# STM32F030.net
KiCad netlist of a schematic drawn in EAGLE
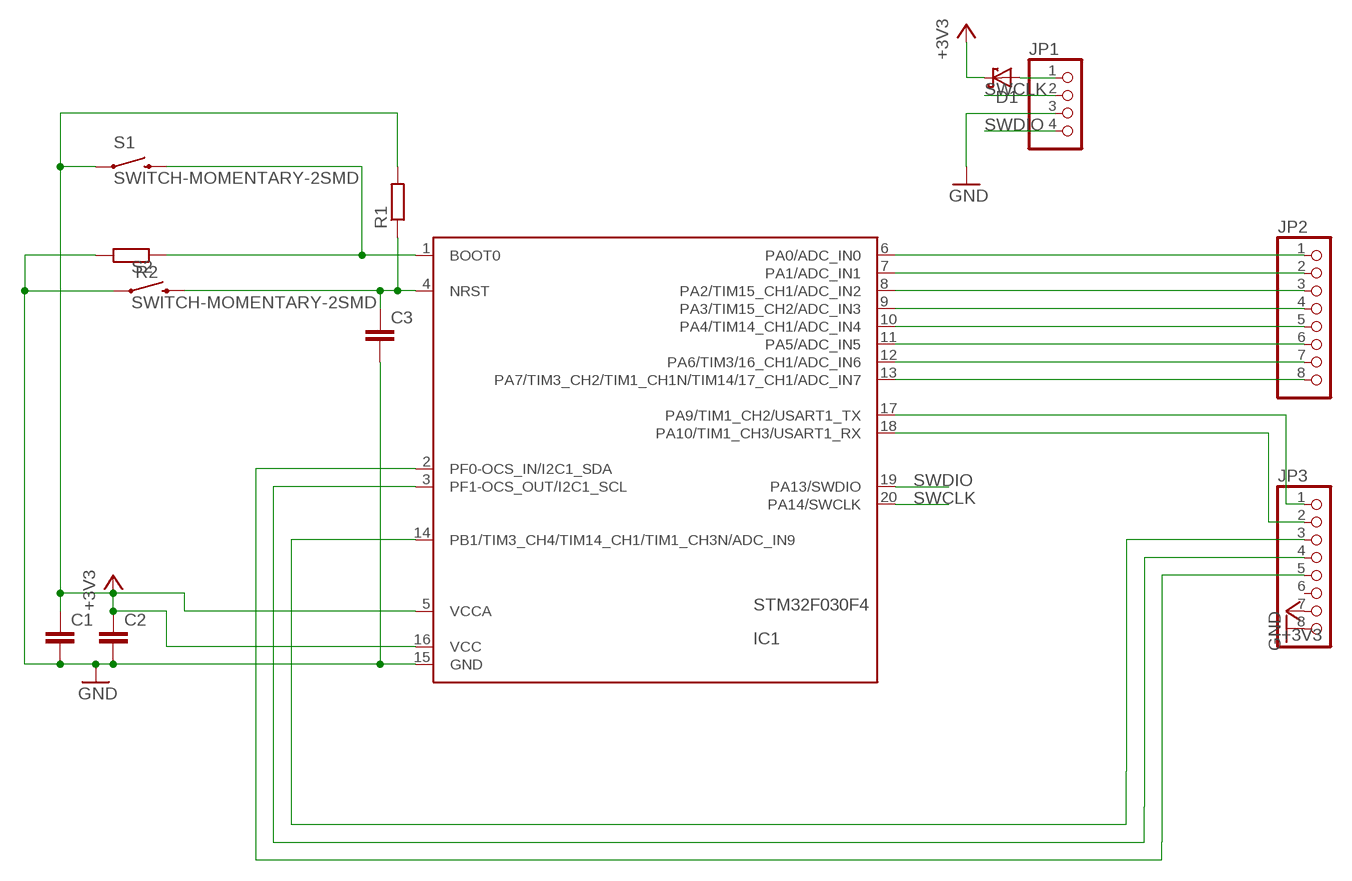
[diagram p0: schematic, sheet 1]

(export (version "E")
  (design (tool "Eeschema 10.0.6"))
  (components
    (comp (ref "C1")
      (value "CAP_0805")
      (footprint "eagle-import:C0805")
      (libsource (lib "eagle-import") (part "CAP_0805"))
    )
    (comp (ref "C2")
      (value "CAP_0805")
      (footprint "eagle-import:C0805")
      (libsource (lib "eagle-import") (part "CAP_0805"))
    )
    (comp (ref "C3")
      (value "CAP_0805")
      (footprint "eagle-import:C0805")
      (libsource (lib "eagle-import") (part "CAP_0805"))
    )
    (comp (ref "D1")
      (value "DIODE-SH_SOD523")
      (footprint "eagle-import:SOD523")
      (libsource (lib "eagle-import") (part "DIODE-SH_SOD523"))
    )
    (comp (ref "IC1")
      (value "STM32F030F4")
      (footprint "eagle-import:TSSOP20")
      (libsource (lib "eagle-import") (part "STM32F030F4"))
    )
    (comp (ref "JP1")
      (value "PINHD-1X4")
      (footprint "eagle-import:1X04")
      (libsource (lib "eagle-import") (part "PINHD-1X4"))
    )
    (comp (ref "JP2")
      (value "PINHD-1X8")
      (footprint "eagle-import:1X08")
      (libsource (lib "eagle-import") (part "PINHD-1X8"))
    )
    (comp (ref "JP3")
      (value "PINHD-1X8")
      (footprint "eagle-import:1X08")
      (libsource (lib "eagle-import") (part "PINHD-1X8"))
    )
    (comp (ref "R1")
      (value "R_0805")
      (footprint "eagle-import:R0805")
      (libsource (lib "eagle-import") (part "R_0805"))
    )
    (comp (ref "R2")
      (value "R_0805")
      (footprint "eagle-import:R0805")
      (libsource (lib "eagle-import") (part "R_0805"))
    )
    (comp (ref "S1")
      (value "SWITCH-MOMENTARY-2SMD")
      (footprint "eagle-import:TACTILE-SWITCH-SMD")
      (libsource (lib "eagle-import") (part "SWITCH-MOMENTARY-2SMD"))
    )
    (comp (ref "S2")
      (value "SWITCH-MOMENTARY-2SMD")
      (footprint "eagle-import:TACTILE-SWITCH-SMD")
      (libsource (lib "eagle-import") (part "SWITCH-MOMENTARY-2SMD"))
    )
  )
  (nets
    (net (code "1") (name "+3V3") (class "Default")
      (node (ref "C1") (pin "1") (pinfunction "1_1") (pintype "passive"))
      (node (ref "C2") (pin "1") (pinfunction "1_1") (pintype "passive"))
      (node (ref "D1") (pin "C") (pinfunction "C_C") (pintype "passive"))
      (node (ref "IC1") (pin "16") (pinfunction "VCC_16") (pintype "power_in"))
      (node (ref "IC1") (pin "5") (pinfunction "VCCA_5") (pintype "power_in"))
      (node (ref "JP3") (pin "7") (pinfunction "7_7") (pintype "passive"))
      (node (ref "R1") (pin "2") (pinfunction "2_2") (pintype "passive"))
      (node (ref "S1") (pin "1") (pinfunction "1_1") (pintype "passive"))
    )
    (net (code "2") (name "/SWCLK") (class "Default")
      (node (ref "IC1") (pin "20") (pinfunction "PA14/SWCLK_20") (pintype "bidirectional"))
      (node (ref "JP1") (pin "2") (pinfunction "2_2") (pintype "passive"))
    )
    (net (code "3") (name "/SWDIO") (class "Default")
      (node (ref "IC1") (pin "19") (pinfunction "PA13/SWDIO_19") (pintype "bidirectional"))
      (node (ref "JP1") (pin "4") (pinfunction "4_4") (pintype "passive"))
    )
    (net (code "4") (name "GND") (class "Default")
      (node (ref "C1") (pin "2") (pinfunction "2_2") (pintype "passive"))
      (node (ref "C2") (pin "2") (pinfunction "2_2") (pintype "passive"))
      (node (ref "C3") (pin "2") (pinfunction "2_2") (pintype "passive"))
      (node (ref "IC1") (pin "15") (pinfunction "GND_15") (pintype "power_in"))
      (node (ref "JP1") (pin "3") (pinfunction "3_3") (pintype "passive"))
      (node (ref "JP3") (pin "8") (pinfunction "8_8") (pintype "passive"))
      (node (ref "R2") (pin "2") (pinfunction "2_2") (pintype "passive"))
      (node (ref "S2") (pin "1") (pinfunction "1_1") (pintype "passive"))
    )
    (net (code "5") (name "Net-(D1-PadA)") (class "Default")
      (node (ref "D1") (pin "A") (pinfunction "A_A") (pintype "passive"))
      (node (ref "JP1") (pin "1") (pinfunction "1_1") (pintype "passive"))
    )
    (net (code "6") (name "Net-(IC1-BOOT0)") (class "Default")
      (node (ref "IC1") (pin "1") (pinfunction "BOOT0_1") (pintype "bidirectional"))
      (node (ref "R2") (pin "1") (pinfunction "1_1") (pintype "passive"))
      (node (ref "S1") (pin "3") (pinfunction "2_3") (pintype "passive"))
    )
    (net (code "7") (name "Net-(IC1-NRST)") (class "Default")
      (node (ref "C3") (pin "1") (pinfunction "1_1") (pintype "passive"))
      (node (ref "IC1") (pin "4") (pinfunction "NRST_4") (pintype "bidirectional"))
      (node (ref "R1") (pin "1") (pinfunction "1_1") (pintype "passive"))
      (node (ref "S2") (pin "3") (pinfunction "2_3") (pintype "passive"))
    )
    (net (code "8") (name "Net-(IC1-PA0{slash}ADC_IN0)") (class "Default")
      (node (ref "IC1") (pin "6") (pinfunction "PA0/ADC_IN0_6") (pintype "bidirectional"))
      (node (ref "JP2") (pin "1") (pinfunction "1_1") (pintype "passive"))
    )
    (net (code "9") (name "Net-(IC1-PA1{slash}ADC_IN1)") (class "Default")
      (node (ref "IC1") (pin "7") (pinfunction "PA1/ADC_IN1_7") (pintype "bidirectional"))
      (node (ref "JP2") (pin "2") (pinfunction "2_2") (pintype "passive"))
    )
    (net (code "10") (name "Net-(IC1-PA2{slash}TIM15_CH1{slash}ADC_IN2)") (class "Default")
      (node (ref "IC1") (pin "8") (pinfunction "PA2/TIM15_CH1/ADC_IN2_8") (pintype "bidirectional"))
      (node (ref "JP2") (pin "3") (pinfunction "3_3") (pintype "passive"))
    )
    (net (code "11") (name "Net-(IC1-PA3{slash}TIM15_CH2{slash}ADC_IN3)") (class "Default")
      (node (ref "IC1") (pin "9") (pinfunction "PA3/TIM15_CH2/ADC_IN3_9") (pintype "bidirectional"))
      (node (ref "JP2") (pin "4") (pinfunction "4_4") (pintype "passive"))
    )
    (net (code "12") (name "Net-(IC1-PA4{slash}TIM14_CH1{slash}ADC_IN4)") (class "Default")
      (node (ref "IC1") (pin "10") (pinfunction "PA4/TIM14_CH1/ADC_IN4_10") (pintype "bidirectional"))
      (node (ref "JP2") (pin "5") (pinfunction "5_5") (pintype "passive"))
    )
    (net (code "13") (name "Net-(IC1-PA5{slash}ADC_IN5)") (class "Default")
      (node (ref "IC1") (pin "11") (pinfunction "PA5/ADC_IN5_11") (pintype "bidirectional"))
      (node (ref "JP2") (pin "6") (pinfunction "6_6") (pintype "passive"))
    )
    (net (code "14") (name "Net-(IC1-PA6{slash}TIM3{slash}16_CH1{slash}ADC_IN6)") (class "Default")
      (node (ref "IC1") (pin "12") (pinfunction "PA6/TIM3/16_CH1/ADC_IN6_12") (pintype "bidirectional"))
      (node (ref "JP2") (pin "7") (pinfunction "7_7") (pintype "passive"))
    )
    (net (code "15") (name "Net-(IC1-PA7{slash}TIM3_CH2{slash}TIM1_CH1N{slash}TIM14{slash}17_CH1{slash}ADC_IN7)") (class "Default")
      (node (ref "IC1") (pin "13") (pinfunction "PA7/TIM3_CH2/TIM1_CH1N/TIM14/17_CH1/ADC_IN7_13") (pintype "bidirectional"))
      (node (ref "JP2") (pin "8") (pinfunction "8_8") (pintype "passive"))
    )
    (net (code "16") (name "Net-(IC1-PA9{slash}TIM1_CH2{slash}USART1_TX)") (class "Default")
      (node (ref "IC1") (pin "17") (pinfunction "PA9/TIM1_CH2/USART1_TX_17") (pintype "bidirectional"))
      (node (ref "JP3") (pin "1") (pinfunction "1_1") (pintype "passive"))
    )
    (net (code "17") (name "Net-(IC1-PA10{slash}TIM1_CH3{slash}USART1_RX)") (class "Default")
      (node (ref "IC1") (pin "18") (pinfunction "PA10/TIM1_CH3/USART1_RX_18") (pintype "bidirectional"))
      (node (ref "JP3") (pin "2") (pinfunction "2_2") (pintype "passive"))
    )
    (net (code "18") (name "Net-(IC1-PB1{slash}TIM3_CH4{slash}TIM14_CH1{slash}TIM1_CH3N{slash}ADC_IN9)") (class "Default")
      (node (ref "IC1") (pin "14") (pinfunction "PB1/TIM3_CH4/TIM14_CH1/TIM1_CH3N/ADC_IN9_14") (pintype "bidirectional"))
      (node (ref "JP3") (pin "3") (pinfunction "3_3") (pintype "passive"))
    )
    (net (code "19") (name "Net-(IC1-PF0-OCS_IN{slash}I2C1_SDA)") (class "Default")
      (node (ref "IC1") (pin "2") (pinfunction "PF0-OCS_IN/I2C1_SDA_2") (pintype "bidirectional"))
      (node (ref "JP3") (pin "5") (pinfunction "5_5") (pintype "passive"))
    )
    (net (code "20") (name "Net-(IC1-PF1-OCS_OUT{slash}I2C1_SCL)") (class "Default")
      (node (ref "IC1") (pin "3") (pinfunction "PF1-OCS_OUT/I2C1_SCL_3") (pintype "bidirectional"))
      (node (ref "JP3") (pin "4") (pinfunction "4_4") (pintype "passive"))
    )
    (net (code "21") (name "unconnected-(JP3-Pad6)") (class "Default")
      (node (ref "JP3") (pin "6") (pinfunction "6_6") (pintype "passive"))
    )
  )
)
